# le_table.net
KiCad netlist of a schematic drawn in EAGLE
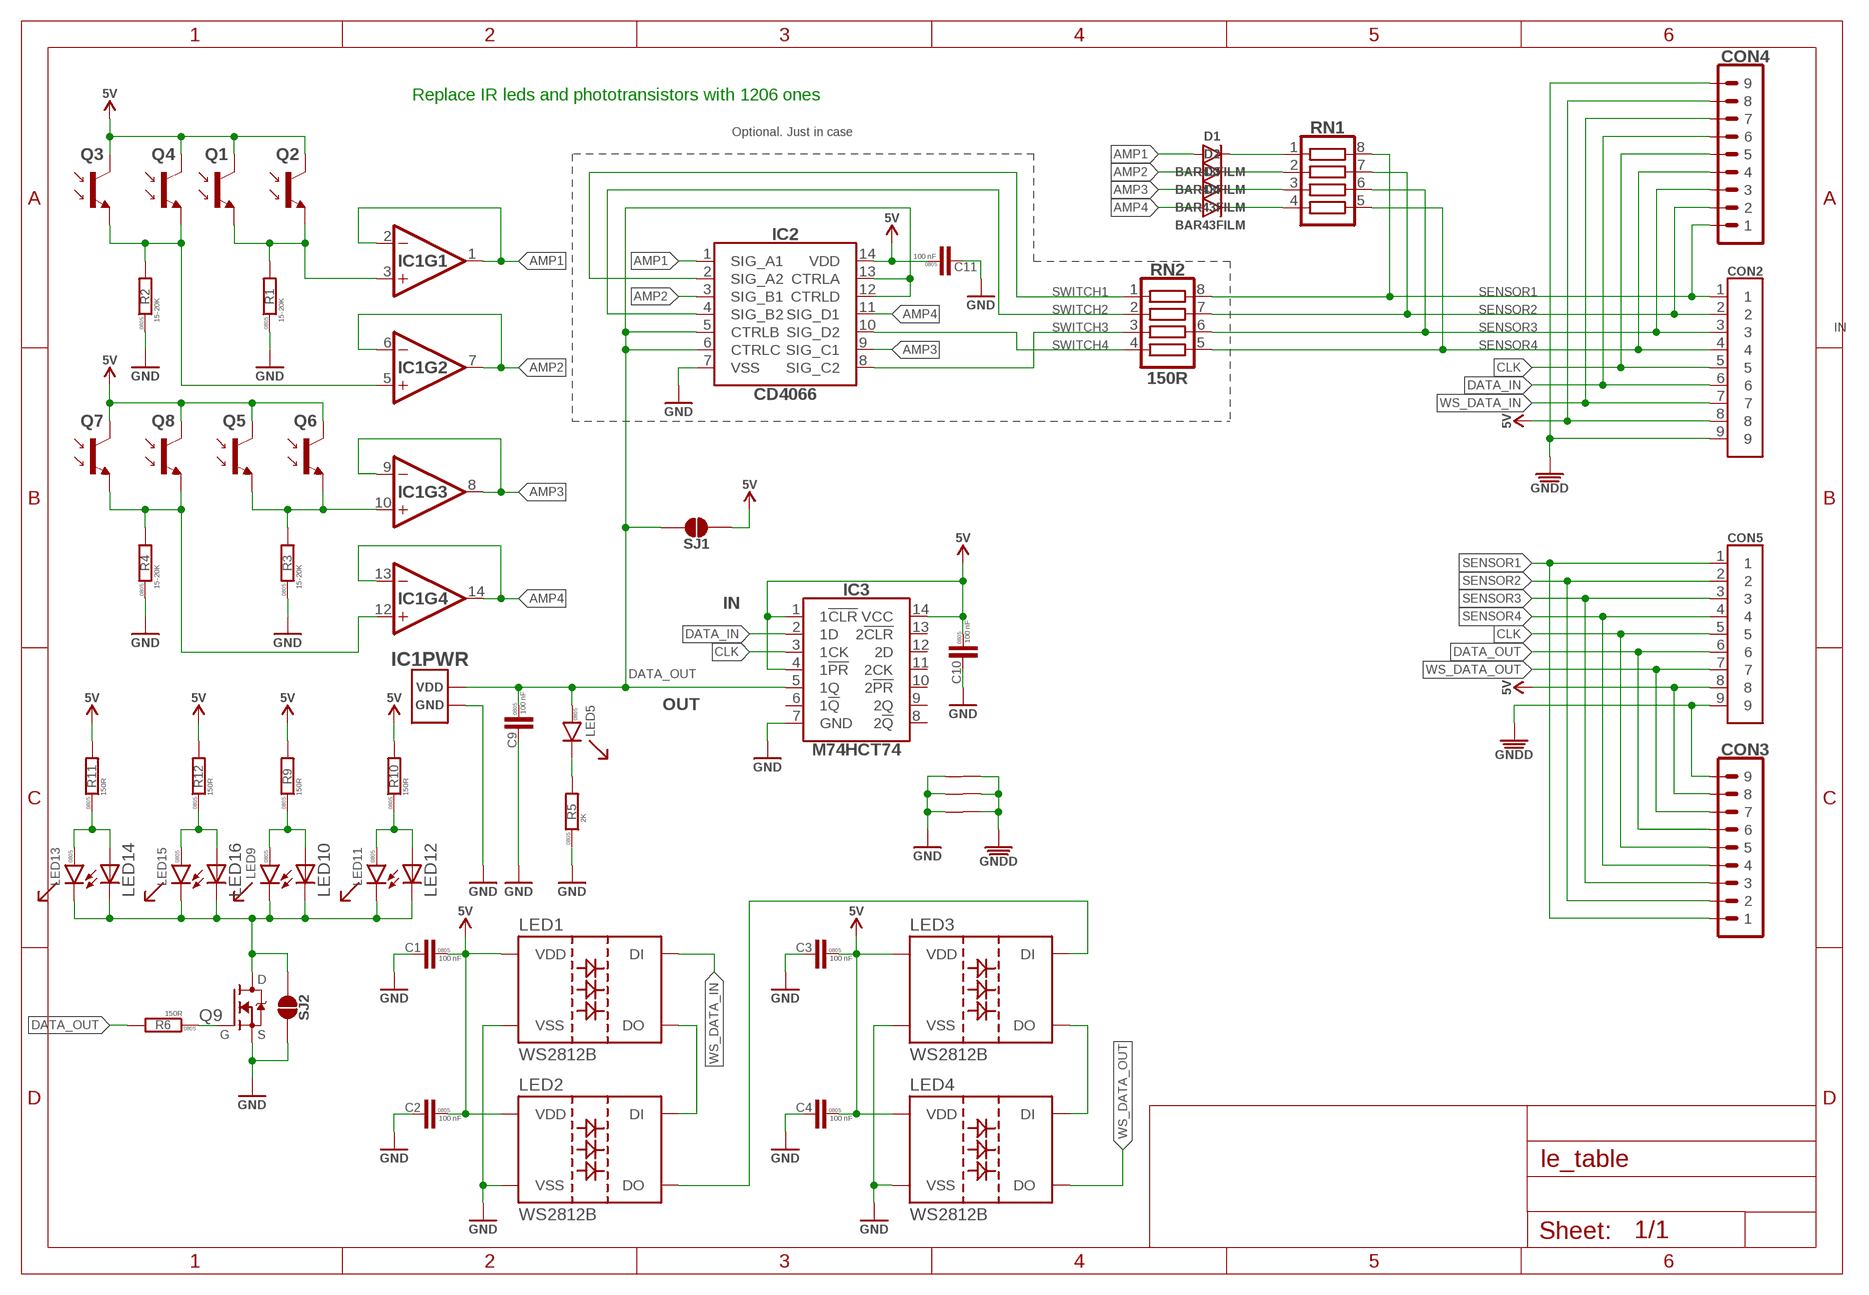
[diagram p0: schematic, sheet 1]

(export (version "E")
  (design (tool "Eeschema 10.0.6"))
  (components
    (comp (ref "C1")
      (value "100 nF")
      (footprint "eagle-import:C0805")
      (libsource (lib "eagle-import") (part "C-0805"))
    )
    (comp (ref "C2")
      (value "100 nF")
      (footprint "eagle-import:C0805")
      (libsource (lib "eagle-import") (part "C-0805"))
    )
    (comp (ref "C3")
      (value "100 nF")
      (footprint "eagle-import:C0805")
      (libsource (lib "eagle-import") (part "C-0805"))
    )
    (comp (ref "C4")
      (value "100 nF")
      (footprint "eagle-import:C0805")
      (libsource (lib "eagle-import") (part "C-0805"))
    )
    (comp (ref "C9")
      (value "100 nF")
      (footprint "eagle-import:C0805")
      (libsource (lib "eagle-import") (part "C-0805"))
    )
    (comp (ref "C10")
      (value "100 nF")
      (footprint "eagle-import:C0805")
      (libsource (lib "eagle-import") (part "C-0805"))
    )
    (comp (ref "C11")
      (value "100 nF")
      (footprint "eagle-import:C0805")
      (libsource (lib "eagle-import") (part "C-0805"))
    )
    (comp (ref "CON2")
      (value "CONNECTOR")
      (footprint "eagle-import:CONNECTOR")
      (libsource (lib "eagle-import") (part "CONNECTOR"))
    )
    (comp (ref "CON3")
      (value "PINHEAD_1X09-2")
      (footprint "eagle-import:1X09-PTH_2")
      (libsource (lib "eagle-import") (part "PINHEAD_1X09-2"))
    )
    (comp (ref "CON4")
      (value "PINHEAD_1X09-2")
      (footprint "eagle-import:1X09-PTH_2")
      (libsource (lib "eagle-import") (part "PINHEAD_1X09-2"))
    )
    (comp (ref "CON5")
      (value "CONNECTOR")
      (footprint "eagle-import:CONNECTOR")
      (libsource (lib "eagle-import") (part "CONNECTOR"))
    )
    (comp (ref "D1")
      (value "BAR43AFILM")
      (footprint "eagle-import:SOT23-3")
      (fields (field (name "MANF") "ST Microelectronics"))
      (libsource (lib "eagle-import") (part "BAR43AFILM"))
    )
    (comp (ref "D2")
      (value "BAR43AFILM")
      (footprint "eagle-import:SOT23-3")
      (fields (field (name "MANF") "ST Microelectronics"))
      (libsource (lib "eagle-import") (part "BAR43AFILM"))
    )
    (comp (ref "D3")
      (value "BAR43AFILM")
      (footprint "eagle-import:SOT23-3")
      (fields (field (name "MANF") "ST Microelectronics"))
      (libsource (lib "eagle-import") (part "BAR43AFILM"))
    )
    (comp (ref "D4")
      (value "BAR43AFILM")
      (footprint "eagle-import:SOT23-3")
      (fields (field (name "MANF") "ST Microelectronics"))
      (libsource (lib "eagle-import") (part "BAR43AFILM"))
    )
    (comp (ref "IC1")
      (value "LM2902DT")
      (footprint "eagle-import:SO-14")
      (libsource (lib "eagle-import") (part "LM2902DT"))
    )
    (comp (ref "IC2")
      (value "CD4066")
      (footprint "eagle-import:SO-14")
      (libsource (lib "eagle-import") (part "CD4066"))
    )
    (comp (ref "IC3")
      (value "M74HCT74")
      (footprint "eagle-import:SO-14")
      (libsource (lib "eagle-import") (part "M74HCT74"))
    )
    (comp (ref "LED1")
      (value "WS2812B")
      (footprint "eagle-import:WS2812B")
      (libsource (lib "eagle-import") (part "WS2812B"))
    )
    (comp (ref "LED2")
      (value "WS2812B")
      (footprint "eagle-import:WS2812B")
      (libsource (lib "eagle-import") (part "WS2812B"))
    )
    (comp (ref "LED3")
      (value "WS2812B")
      (footprint "eagle-import:WS2812B")
      (libsource (lib "eagle-import") (part "WS2812B"))
    )
    (comp (ref "LED4")
      (value "WS2812B")
      (footprint "eagle-import:WS2812B")
      (libsource (lib "eagle-import") (part "WS2812B"))
    )
    (comp (ref "LED5")
      (value "LED-0805")
      (footprint "eagle-import:0805_LED")
      (fields (field (name "PACKAGE") "0805"))
      (libsource (lib "eagle-import") (part "LED-0805"))
    )
    (comp (ref "LED9")
      (value "LED-0805")
      (footprint "eagle-import:0805_LED")
      (fields (field (name "PACKAGE") "0805"))
      (libsource (lib "eagle-import") (part "LED-0805"))
    )
    (comp (ref "LED10")
      (value "LED-3MM")
      (footprint "eagle-import:LED-3MM")
      (fields (field (name "ASSEMBLY") "SPECIAL"))
      (libsource (lib "eagle-import") (part "LED-3MM"))
    )
    (comp (ref "LED11")
      (value "LED-0805")
      (footprint "eagle-import:0805_LED")
      (fields (field (name "PACKAGE") "0805"))
      (libsource (lib "eagle-import") (part "LED-0805"))
    )
    (comp (ref "LED12")
      (value "LED-3MM")
      (footprint "eagle-import:LED-3MM")
      (fields (field (name "ASSEMBLY") "SPECIAL"))
      (libsource (lib "eagle-import") (part "LED-3MM"))
    )
    (comp (ref "LED13")
      (value "LED-0805")
      (footprint "eagle-import:0805_LED")
      (fields (field (name "PACKAGE") "0805"))
      (libsource (lib "eagle-import") (part "LED-0805"))
    )
    (comp (ref "LED14")
      (value "LED-3MM")
      (footprint "eagle-import:LED-3MM")
      (fields (field (name "ASSEMBLY") "SPECIAL"))
      (libsource (lib "eagle-import") (part "LED-3MM"))
    )
    (comp (ref "LED15")
      (value "LED-0805")
      (footprint "eagle-import:0805_LED")
      (fields (field (name "PACKAGE") "0805"))
      (libsource (lib "eagle-import") (part "LED-0805"))
    )
    (comp (ref "LED16")
      (value "LED-3MM")
      (footprint "eagle-import:LED-3MM")
      (fields (field (name "ASSEMBLY") "SPECIAL"))
      (libsource (lib "eagle-import") (part "LED-3MM"))
    )
    (comp (ref "Q1")
      (value "PHOTOTRANSISTOR-3MM")
      (footprint "eagle-import:LED-3MM")
      (libsource (lib "eagle-import") (part "PHOTOTRANSISTOR-3MM"))
    )
    (comp (ref "Q2")
      (value "PHOTOTRANSISTOR-0805")
      (footprint "eagle-import:0805")
      (libsource (lib "eagle-import") (part "PHOTOTRANSISTOR-0805"))
    )
    (comp (ref "Q3")
      (value "PHOTOTRANSISTOR-3MM")
      (footprint "eagle-import:LED-3MM")
      (libsource (lib "eagle-import") (part "PHOTOTRANSISTOR-3MM"))
    )
    (comp (ref "Q4")
      (value "PHOTOTRANSISTOR-0805")
      (footprint "eagle-import:0805")
      (libsource (lib "eagle-import") (part "PHOTOTRANSISTOR-0805"))
    )
    (comp (ref "Q5")
      (value "PHOTOTRANSISTOR-3MM")
      (footprint "eagle-import:LED-3MM")
      (libsource (lib "eagle-import") (part "PHOTOTRANSISTOR-3MM"))
    )
    (comp (ref "Q6")
      (value "PHOTOTRANSISTOR-0805")
      (footprint "eagle-import:0805")
      (libsource (lib "eagle-import") (part "PHOTOTRANSISTOR-0805"))
    )
    (comp (ref "Q7")
      (value "PHOTOTRANSISTOR-3MM")
      (footprint "eagle-import:LED-3MM")
      (libsource (lib "eagle-import") (part "PHOTOTRANSISTOR-3MM"))
    )
    (comp (ref "Q8")
      (value "PHOTOTRANSISTOR-0805")
      (footprint "eagle-import:0805")
      (libsource (lib "eagle-import") (part "PHOTOTRANSISTOR-0805"))
    )
    (comp (ref "Q9")
      (value "IRLML2502-SOT23")
      (footprint "eagle-import:SOT23B-3")
      (fields (field (name "MANF") "Infineon Technologies"))
      (libsource (lib "eagle-import") (part "IRLML2502-SOT23"))
    )
    (comp (ref "R1")
      (value "15-20K")
      (footprint "eagle-import:R0805")
      (libsource (lib "eagle-import") (part "R-0805"))
    )
    (comp (ref "R2")
      (value "15-20K")
      (footprint "eagle-import:R0805")
      (libsource (lib "eagle-import") (part "R-0805"))
    )
    (comp (ref "R3")
      (value "15-20K")
      (footprint "eagle-import:R0805")
      (libsource (lib "eagle-import") (part "R-0805"))
    )
    (comp (ref "R4")
      (value "15-20K")
      (footprint "eagle-import:R0805")
      (libsource (lib "eagle-import") (part "R-0805"))
    )
    (comp (ref "R5")
      (value "2K")
      (footprint "eagle-import:R0805")
      (libsource (lib "eagle-import") (part "R-0805"))
    )
    (comp (ref "R6")
      (value "150R")
      (footprint "eagle-import:R0805")
      (libsource (lib "eagle-import") (part "R-0805"))
    )
    (comp (ref "R9")
      (value "150R")
      (footprint "eagle-import:R0805")
      (libsource (lib "eagle-import") (part "R-0805"))
    )
    (comp (ref "R10")
      (value "150R")
      (footprint "eagle-import:R0805")
      (libsource (lib "eagle-import") (part "R-0805"))
    )
    (comp (ref "R11")
      (value "150R")
      (footprint "eagle-import:R0805")
      (libsource (lib "eagle-import") (part "R-0805"))
    )
    (comp (ref "R12")
      (value "150R")
      (footprint "eagle-import:R0805")
      (libsource (lib "eagle-import") (part "R-0805"))
    )
    (comp (ref "RN1")
      (value "RESISTOR_ARRAY")
      (footprint "eagle-import:CAT16-J4")
      (libsource (lib "eagle-import") (part "RESISTOR_ARRAY"))
    )
    (comp (ref "RN2")
      (value "150R")
      (footprint "eagle-import:CAT16-J4")
      (libsource (lib "eagle-import") (part "RESISTOR_ARRAY"))
    )
    (comp (ref "SJ1")
      (value "SOLDER_JOINT")
      (footprint "eagle-import:RES_0")
      (libsource (lib "eagle-import") (part "SOLDER_JOINT"))
    )
    (comp (ref "SJ2")
      (value "SOLDER_JOINT")
      (footprint "eagle-import:RES_0")
      (libsource (lib "eagle-import") (part "SOLDER_JOINT"))
    )
    (comp (ref "U$3")
      (value "CONNECTION")
      (footprint "eagle-import:CONNECTION")
      (libsource (lib "eagle-import") (part "CONNECTION"))
    )
    (comp (ref "U$6")
      (value "CONNECTION")
      (footprint "eagle-import:CONNECTION")
      (libsource (lib "eagle-import") (part "CONNECTION"))
    )
    (comp (ref "U$7")
      (value "CONNECTION")
      (footprint "eagle-import:CONNECTION")
      (libsource (lib "eagle-import") (part "CONNECTION"))
    )
  )
  (nets
    (net (code "1") (name "/SWITCH1") (class "Default")
      (node (ref "IC2") (pin "2") (pinfunction "SIG_A2_2") (pintype "bidirectional"))
      (node (ref "RN2") (pin "1") (pinfunction "1_1") (pintype "passive"))
    )
    (net (code "2") (name "/SWITCH2") (class "Default")
      (node (ref "IC2") (pin "4") (pinfunction "SIG_B2_4") (pintype "bidirectional"))
      (node (ref "RN2") (pin "2") (pinfunction "2_2") (pintype "passive"))
    )
    (net (code "3") (name "/SWITCH3") (class "Default")
      (node (ref "IC2") (pin "8") (pinfunction "SIG_C2_8") (pintype "bidirectional"))
      (node (ref "RN2") (pin "3") (pinfunction "3_3") (pintype "passive"))
    )
    (net (code "4") (name "/SWITCH4") (class "Default")
      (node (ref "IC2") (pin "10") (pinfunction "SIG_D2_10") (pintype "bidirectional"))
      (node (ref "RN2") (pin "4") (pinfunction "4_4") (pintype "passive"))
    )
    (net (code "5") (name "5V") (class "Default")
      (node (ref "C1") (pin "1") (pinfunction "1_1") (pintype "passive"))
      (node (ref "C10") (pin "1") (pinfunction "1_1") (pintype "passive"))
      (node (ref "C11") (pin "1") (pinfunction "1_1") (pintype "passive"))
      (node (ref "C2") (pin "1") (pinfunction "1_1") (pintype "passive"))
      (node (ref "C3") (pin "1") (pinfunction "1_1") (pintype "passive"))
      (node (ref "C4") (pin "1") (pinfunction "1_1") (pintype "passive"))
      (node (ref "CON2") (pin "8") (pinfunction "8_8") (pintype "bidirectional"))
      (node (ref "CON3") (pin "8") (pinfunction "8_8") (pintype "passive"))
      (node (ref "CON4") (pin "8") (pinfunction "8_8") (pintype "passive"))
      (node (ref "CON5") (pin "8") (pinfunction "8_8") (pintype "bidirectional"))
      (node (ref "IC2") (pin "14") (pinfunction "VDD_14") (pintype "bidirectional"))
      (node (ref "IC3") (pin "1") (pinfunction "1~{CLR}_1") (pintype "bidirectional"))
      (node (ref "IC3") (pin "14") (pinfunction "VCC_14") (pintype "bidirectional"))
      (node (ref "IC3") (pin "4") (pinfunction "1~{PR}_4") (pintype "bidirectional"))
      (node (ref "LED1") (pin "1") (pinfunction "VDD_1") (pintype "bidirectional"))
      (node (ref "LED2") (pin "1") (pinfunction "VDD_1") (pintype "bidirectional"))
      (node (ref "LED3") (pin "1") (pinfunction "VDD_1") (pintype "bidirectional"))
      (node (ref "LED4") (pin "1") (pinfunction "VDD_1") (pintype "bidirectional"))
      (node (ref "Q1") (pin "A") (pinfunction "C_A") (pintype "passive"))
      (node (ref "Q2") (pin "1") (pinfunction "C_1") (pintype "passive"))
      (node (ref "Q3") (pin "A") (pinfunction "C_A") (pintype "passive"))
      (node (ref "Q4") (pin "1") (pinfunction "C_1") (pintype "passive"))
      (node (ref "Q5") (pin "A") (pinfunction "C_A") (pintype "passive"))
      (node (ref "Q6") (pin "1") (pinfunction "C_1") (pintype "passive"))
      (node (ref "Q7") (pin "A") (pinfunction "C_A") (pintype "passive"))
      (node (ref "Q8") (pin "1") (pinfunction "C_1") (pintype "passive"))
      (node (ref "R10") (pin "2") (pinfunction "2_2") (pintype "passive"))
      (node (ref "R11") (pin "2") (pinfunction "2_2") (pintype "passive"))
      (node (ref "R12") (pin "2") (pinfunction "2_2") (pintype "passive"))
      (node (ref "R9") (pin "2") (pinfunction "2_2") (pintype "passive"))
      (node (ref "SJ1") (pin "1") (pinfunction "1_1") (pintype "passive"))
    )
    (net (code "6") (name "AMP1") (class "Default")
      (node (ref "D1") (pin "1") (pinfunction "A_1") (pintype "passive"))
      (node (ref "IC1") (pin "1") (pinfunction "OUT_1") (pintype "output"))
      (node (ref "IC1") (pin "2") (pinfunction "-IN_2") (pintype "input"))
      (node (ref "IC2") (pin "1") (pinfunction "SIG_A1_1") (pintype "bidirectional"))
    )
    (net (code "7") (name "AMP2") (class "Default")
      (node (ref "D2") (pin "1") (pinfunction "A_1") (pintype "passive"))
      (node (ref "IC1") (pin "6") (pinfunction "-IN_6") (pintype "input"))
      (node (ref "IC1") (pin "7") (pinfunction "OUT_7") (pintype "output"))
      (node (ref "IC2") (pin "3") (pinfunction "SIG_B1_3") (pintype "bidirectional"))
    )
    (net (code "8") (name "AMP3") (class "Default")
      (node (ref "D3") (pin "1") (pinfunction "A_1") (pintype "passive"))
      (node (ref "IC1") (pin "8") (pinfunction "OUT_8") (pintype "output"))
      (node (ref "IC1") (pin "9") (pinfunction "-IN_9") (pintype "input"))
      (node (ref "IC2") (pin "9") (pinfunction "SIG_C1_9") (pintype "bidirectional"))
    )
    (net (code "9") (name "AMP4") (class "Default")
      (node (ref "D4") (pin "1") (pinfunction "A_1") (pintype "passive"))
      (node (ref "IC1") (pin "13") (pinfunction "-IN_13") (pintype "input"))
      (node (ref "IC1") (pin "14") (pinfunction "OUT_14") (pintype "output"))
      (node (ref "IC2") (pin "11") (pinfunction "SIG_D1_11") (pintype "bidirectional"))
    )
    (net (code "10") (name "CLK") (class "Default")
      (node (ref "CON2") (pin "5") (pinfunction "5_5") (pintype "bidirectional"))
      (node (ref "CON3") (pin "5") (pinfunction "5_5") (pintype "passive"))
      (node (ref "CON4") (pin "5") (pinfunction "5_5") (pintype "passive"))
      (node (ref "CON5") (pin "5") (pinfunction "5_5") (pintype "bidirectional"))
      (node (ref "IC3") (pin "3") (pinfunction "1CK_3") (pintype "bidirectional"))
    )
    (net (code "11") (name "DATA_IN") (class "Default")
      (node (ref "CON2") (pin "6") (pinfunction "6_6") (pintype "bidirectional"))
      (node (ref "CON4") (pin "6") (pinfunction "6_6") (pintype "passive"))
      (node (ref "IC3") (pin "2") (pinfunction "1D_2") (pintype "bidirectional"))
    )
    (net (code "12") (name "DATA_OUT") (class "Default")
      (node (ref "C9") (pin "1") (pinfunction "1_1") (pintype "passive"))
      (node (ref "CON3") (pin "6") (pinfunction "6_6") (pintype "passive"))
      (node (ref "CON5") (pin "6") (pinfunction "6_6") (pintype "bidirectional"))
      (node (ref "IC1") (pin "4") (pinfunction "VDD_4") (pintype "bidirectional"))
      (node (ref "IC2") (pin "12") (pinfunction "CTRLD_12") (pintype "bidirectional"))
      (node (ref "IC2") (pin "13") (pinfunction "CTRLA_13") (pintype "bidirectional"))
      (node (ref "IC2") (pin "5") (pinfunction "CTRLB_5") (pintype "bidirectional"))
      (node (ref "IC2") (pin "6") (pinfunction "CTRLC_6") (pintype "bidirectional"))
      (node (ref "IC3") (pin "5") (pinfunction "1Q_5") (pintype "bidirectional"))
      (node (ref "LED5") (pin "A") (pinfunction "A_A") (pintype "bidirectional"))
      (node (ref "R6") (pin "2") (pinfunction "2_2") (pintype "passive"))
      (node (ref "SJ1") (pin "2") (pinfunction "2_2") (pintype "passive"))
    )
    (net (code "13") (name "GND") (class "Default")
      (node (ref "C1") (pin "2") (pinfunction "2_2") (pintype "passive"))
      (node (ref "C10") (pin "2") (pinfunction "2_2") (pintype "passive"))
      (node (ref "C11") (pin "2") (pinfunction "2_2") (pintype "passive"))
      (node (ref "C2") (pin "2") (pinfunction "2_2") (pintype "passive"))
      (node (ref "C3") (pin "2") (pinfunction "2_2") (pintype "passive"))
      (node (ref "C4") (pin "2") (pinfunction "2_2") (pintype "passive"))
      (node (ref "C9") (pin "2") (pinfunction "2_2") (pintype "passive"))
      (node (ref "IC1") (pin "11") (pinfunction "GND_11") (pintype "bidirectional"))
      (node (ref "IC2") (pin "7") (pinfunction "VSS_7") (pintype "bidirectional"))
      (node (ref "IC3") (pin "7") (pinfunction "GND_7") (pintype "bidirectional"))
      (node (ref "LED1") (pin "3") (pinfunction "VSS_3") (pintype "bidirectional"))
      (node (ref "LED2") (pin "3") (pinfunction "VSS_3") (pintype "bidirectional"))
      (node (ref "LED3") (pin "3") (pinfunction "VSS_3") (pintype "bidirectional"))
      (node (ref "LED4") (pin "3") (pinfunction "VSS_3") (pintype "bidirectional"))
      (node (ref "Q9") (pin "2") (pinfunction "S_2") (pintype "passive"))
      (node (ref "R1") (pin "1") (pinfunction "1_1") (pintype "passive"))
      (node (ref "R2") (pin "1") (pinfunction "1_1") (pintype "passive"))
      (node (ref "R3") (pin "1") (pinfunction "1_1") (pintype "passive"))
      (node (ref "R4") (pin "1") (pinfunction "1_1") (pintype "passive"))
      (node (ref "R5") (pin "1") (pinfunction "1_1") (pintype "passive"))
      (node (ref "SJ2") (pin "2") (pinfunction "2_2") (pintype "passive"))
      (node (ref "U$3") (pin "P$2") (pinfunction "P$2_P$2") (pintype "bidirectional"))
      (node (ref "U$6") (pin "P$2") (pinfunction "P$2_P$2") (pintype "bidirectional"))
      (node (ref "U$7") (pin "P$2") (pinfunction "P$2_P$2") (pintype "bidirectional"))
    )
    (net (code "14") (name "GNDD") (class "Default")
      (node (ref "CON2") (pin "9") (pinfunction "9_9") (pintype "bidirectional"))
      (node (ref "CON3") (pin "9") (pinfunction "9_9") (pintype "passive"))
      (node (ref "CON4") (pin "9") (pinfunction "9_9") (pintype "passive"))
      (node (ref "CON5") (pin "9") (pinfunction "9_9") (pintype "bidirectional"))
      (node (ref "U$3") (pin "P$1") (pinfunction "P$1_P$1") (pintype "bidirectional"))
      (node (ref "U$6") (pin "P$1") (pinfunction "P$1_P$1") (pintype "bidirectional"))
      (node (ref "U$7") (pin "P$1") (pinfunction "P$1_P$1") (pintype "bidirectional"))
    )
    (net (code "15") (name "Net-(D1-C)") (class "Default")
      (node (ref "D1") (pin "3") (pinfunction "C_3") (pintype "passive"))
      (node (ref "RN1") (pin "1") (pinfunction "1_1") (pintype "passive"))
    )
    (net (code "16") (name "Net-(D2-C)") (class "Default")
      (node (ref "D2") (pin "3") (pinfunction "C_3") (pintype "passive"))
      (node (ref "RN1") (pin "2") (pinfunction "2_2") (pintype "passive"))
    )
    (net (code "17") (name "Net-(D3-C)") (class "Default")
      (node (ref "D3") (pin "3") (pinfunction "C_3") (pintype "passive"))
      (node (ref "RN1") (pin "3") (pinfunction "3_3") (pintype "passive"))
    )
    (net (code "18") (name "Net-(D4-C)") (class "Default")
      (node (ref "D4") (pin "3") (pinfunction "C_3") (pintype "passive"))
      (node (ref "RN1") (pin "4") (pinfunction "4_4") (pintype "passive"))
    )
    (net (code "19") (name "Net-(IC1A-+IN)") (class "Default")
      (node (ref "IC1") (pin "3") (pinfunction "+IN_3") (pintype "input"))
      (node (ref "Q1") (pin "K") (pinfunction "E_K") (pintype "passive"))
      (node (ref "Q2") (pin "2") (pinfunction "E_2") (pintype "passive"))
      (node (ref "R1") (pin "2") (pinfunction "2_2") (pintype "passive"))
    )
    (net (code "20") (name "Net-(IC1B-+IN)") (class "Default")
      (node (ref "IC1") (pin "5") (pinfunction "+IN_5") (pintype "input"))
      (node (ref "Q3") (pin "K") (pinfunction "E_K") (pintype "passive"))
      (node (ref "Q4") (pin "2") (pinfunction "E_2") (pintype "passive"))
      (node (ref "R2") (pin "2") (pinfunction "2_2") (pintype "passive"))
    )
    (net (code "21") (name "Net-(IC1C-+IN)") (class "Default")
      (node (ref "IC1") (pin "10") (pinfunction "+IN_10") (pintype "input"))
      (node (ref "Q5") (pin "K") (pinfunction "E_K") (pintype "passive"))
      (node (ref "Q6") (pin "2") (pinfunction "E_2") (pintype "passive"))
      (node (ref "R3") (pin "2") (pinfunction "2_2") (pintype "passive"))
    )
    (net (code "22") (name "Net-(IC1D-+IN)") (class "Default")
      (node (ref "IC1") (pin "12") (pinfunction "+IN_12") (pintype "input"))
      (node (ref "Q7") (pin "K") (pinfunction "E_K") (pintype "passive"))
      (node (ref "Q8") (pin "2") (pinfunction "E_2") (pintype "passive"))
      (node (ref "R4") (pin "2") (pinfunction "2_2") (pintype "passive"))
    )
    (net (code "23") (name "Net-(LED1-DO)") (class "Default")
      (node (ref "LED1") (pin "2") (pinfunction "DO_2") (pintype "bidirectional"))
      (node (ref "LED2") (pin "4") (pinfunction "DI_4") (pintype "bidirectional"))
    )
    (net (code "24") (name "Net-(LED2-DO)") (class "Default")
      (node (ref "LED2") (pin "2") (pinfunction "DO_2") (pintype "bidirectional"))
      (node (ref "LED3") (pin "4") (pinfunction "DI_4") (pintype "bidirectional"))
    )
    (net (code "25") (name "Net-(LED3-DO)") (class "Default")
      (node (ref "LED3") (pin "2") (pinfunction "DO_2") (pintype "bidirectional"))
      (node (ref "LED4") (pin "4") (pinfunction "DI_4") (pintype "bidirectional"))
    )
    (net (code "26") (name "Net-(LED5-PadC)") (class "Default")
      (node (ref "LED5") (pin "C") (pinfunction "C_C") (pintype "bidirectional"))
      (node (ref "R5") (pin "2") (pinfunction "2_2") (pintype "passive"))
    )
    (net (code "27") (name "Net-(LED10-C)") (class "Default")
      (node (ref "LED10") (pin "K") (pinfunction "C_K") (pintype "passive"))
      (node (ref "LED11") (pin "C") (pinfunction "C_C") (pintype "bidirectional"))
      (node (ref "LED12") (pin "K") (pinfunction "C_K") (pintype "passive"))
      (node (ref "LED13") (pin "C") (pinfunction "C_C") (pintype "bidirectional"))
      (node (ref "LED14") (pin "K") (pinfunction "C_K") (pintype "passive"))
      (node (ref "LED15") (pin "C") (pinfunction "C_C") (pintype "bidirectional"))
      (node (ref "LED16") (pin "K") (pinfunction "C_K") (pintype "passive"))
      (node (ref "LED9") (pin "C") (pinfunction "C_C") (pintype "bidirectional"))
      (node (ref "Q9") (pin "3") (pinfunction "D_3") (pintype "passive"))
      (node (ref "SJ2") (pin "1") (pinfunction "1_1") (pintype "passive"))
    )
    (net (code "28") (name "Net-(LED10-PadA)") (class "Default")
      (node (ref "LED10") (pin "A") (pinfunction "A_A") (pintype "passive"))
      (node (ref "LED9") (pin "A") (pinfunction "A_A") (pintype "bidirectional"))
      (node (ref "R9") (pin "1") (pinfunction "1_1") (pintype "passive"))
    )
    (net (code "29") (name "Net-(LED11-PadA)") (class "Default")
      (node (ref "LED11") (pin "A") (pinfunction "A_A") (pintype "bidirectional"))
      (node (ref "LED12") (pin "A") (pinfunction "A_A") (pintype "passive"))
      (node (ref "R10") (pin "1") (pinfunction "1_1") (pintype "passive"))
    )
    (net (code "30") (name "Net-(LED13-PadA)") (class "Default")
      (node (ref "LED13") (pin "A") (pinfunction "A_A") (pintype "bidirectional"))
      (node (ref "LED14") (pin "A") (pinfunction "A_A") (pintype "passive"))
      (node (ref "R11") (pin "1") (pinfunction "1_1") (pintype "passive"))
    )
    (net (code "31") (name "Net-(LED15-PadA)") (class "Default")
      (node (ref "LED15") (pin "A") (pinfunction "A_A") (pintype "bidirectional"))
      (node (ref "LED16") (pin "A") (pinfunction "A_A") (pintype "passive"))
      (node (ref "R12") (pin "1") (pinfunction "1_1") (pintype "passive"))
    )
    (net (code "32") (name "Net-(Q9-G)") (class "Default")
      (node (ref "Q9") (pin "1") (pinfunction "G_1") (pintype "passive"))
      (node (ref "R6") (pin "1") (pinfunction "1_1") (pintype "passive"))
    )
    (net (code "33") (name "SENSOR1") (class "Default")
      (node (ref "CON2") (pin "1") (pinfunction "1_1") (pintype "bidirectional"))
      (node (ref "CON3") (pin "1") (pinfunction "1_1") (pintype "passive"))
      (node (ref "CON4") (pin "1") (pinfunction "1_1") (pintype "passive"))
      (node (ref "CON5") (pin "1") (pinfunction "1_1") (pintype "bidirectional"))
      (node (ref "RN1") (pin "8") (pinfunction "8_8") (pintype "passive"))
      (node (ref "RN2") (pin "8") (pinfunction "8_8") (pintype "passive"))
    )
    (net (code "34") (name "SENSOR2") (class "Default")
      (node (ref "CON2") (pin "2") (pinfunction "2_2") (pintype "bidirectional"))
      (node (ref "CON3") (pin "2") (pinfunction "2_2") (pintype "passive"))
      (node (ref "CON4") (pin "2") (pinfunction "2_2") (pintype "passive"))
      (node (ref "CON5") (pin "2") (pinfunction "2_2") (pintype "bidirectional"))
      (node (ref "RN1") (pin "7") (pinfunction "7_7") (pintype "passive"))
      (node (ref "RN2") (pin "7") (pinfunction "7_7") (pintype "passive"))
    )
    (net (code "35") (name "SENSOR3") (class "Default")
      (node (ref "CON2") (pin "3") (pinfunction "3_3") (pintype "bidirectional"))
      (node (ref "CON3") (pin "3") (pinfunction "3_3") (pintype "passive"))
      (node (ref "CON4") (pin "3") (pinfunction "3_3") (pintype "passive"))
      (node (ref "CON5") (pin "3") (pinfunction "3_3") (pintype "bidirectional"))
      (node (ref "RN1") (pin "6") (pinfunction "6_6") (pintype "passive"))
      (node (ref "RN2") (pin "6") (pinfunction "6_6") (pintype "passive"))
    )
    (net (code "36") (name "SENSOR4") (class "Default")
      (node (ref "CON2") (pin "4") (pinfunction "4_4") (pintype "bidirectional"))
      (node (ref "CON3") (pin "4") (pinfunction "4_4") (pintype "passive"))
      (node (ref "CON4") (pin "4") (pinfunction "4_4") (pintype "passive"))
      (node (ref "CON5") (pin "4") (pinfunction "4_4") (pintype "bidirectional"))
      (node (ref "RN1") (pin "5") (pinfunction "5_5") (pintype "passive"))
      (node (ref "RN2") (pin "5") (pinfunction "5_5") (pintype "passive"))
    )
    (net (code "37") (name "WS_DATA_IN") (class "Default")
      (node (ref "CON2") (pin "7") (pinfunction "7_7") (pintype "bidirectional"))
      (node (ref "CON4") (pin "7") (pinfunction "7_7") (pintype "passive"))
      (node (ref "LED1") (pin "4") (pinfunction "DI_4") (pintype "bidirectional"))
    )
    (net (code "38") (name "WS_DATA_OUT") (class "Default")
      (node (ref "CON3") (pin "7") (pinfunction "7_7") (pintype "passive"))
      (node (ref "CON5") (pin "7") (pinfunction "7_7") (pintype "bidirectional"))
      (node (ref "LED4") (pin "2") (pinfunction "DO_2") (pintype "bidirectional"))
    )
    (net (code "39") (name "unconnected-(IC3-1~{Q}-Pad6)") (class "Default")
      (node (ref "IC3") (pin "6") (pinfunction "1~{Q}_6") (pintype "bidirectional"))
    )
    (net (code "40") (name "unconnected-(IC3-2CK-Pad11)") (class "Default")
      (node (ref "IC3") (pin "11") (pinfunction "2CK_11") (pintype "bidirectional"))
    )
    (net (code "41") (name "unconnected-(IC3-2D-Pad12)") (class "Default")
      (node (ref "IC3") (pin "12") (pinfunction "2D_12") (pintype "bidirectional"))
    )
    (net (code "42") (name "unconnected-(IC3-2Q-Pad9)") (class "Default")
      (node (ref "IC3") (pin "9") (pinfunction "2Q_9") (pintype "bidirectional"))
    )
    (net (code "43") (name "unconnected-(IC3-2~{CLR}-Pad13)") (class "Default")
      (node (ref "IC3") (pin "13") (pinfunction "2~{CLR}_13") (pintype "bidirectional"))
    )
    (net (code "44") (name "unconnected-(IC3-2~{PR}-Pad10)") (class "Default")
      (node (ref "IC3") (pin "10") (pinfunction "2~{PR}_10") (pintype "bidirectional"))
    )
    (net (code "45") (name "unconnected-(IC3-2~{Q}-Pad8)") (class "Default")
      (node (ref "IC3") (pin "8") (pinfunction "2~{Q}_8") (pintype "bidirectional"))
    )
  )
)
